# QRE1113_analogico_v11.net
KiCad netlist of a schematic drawn in EAGLE
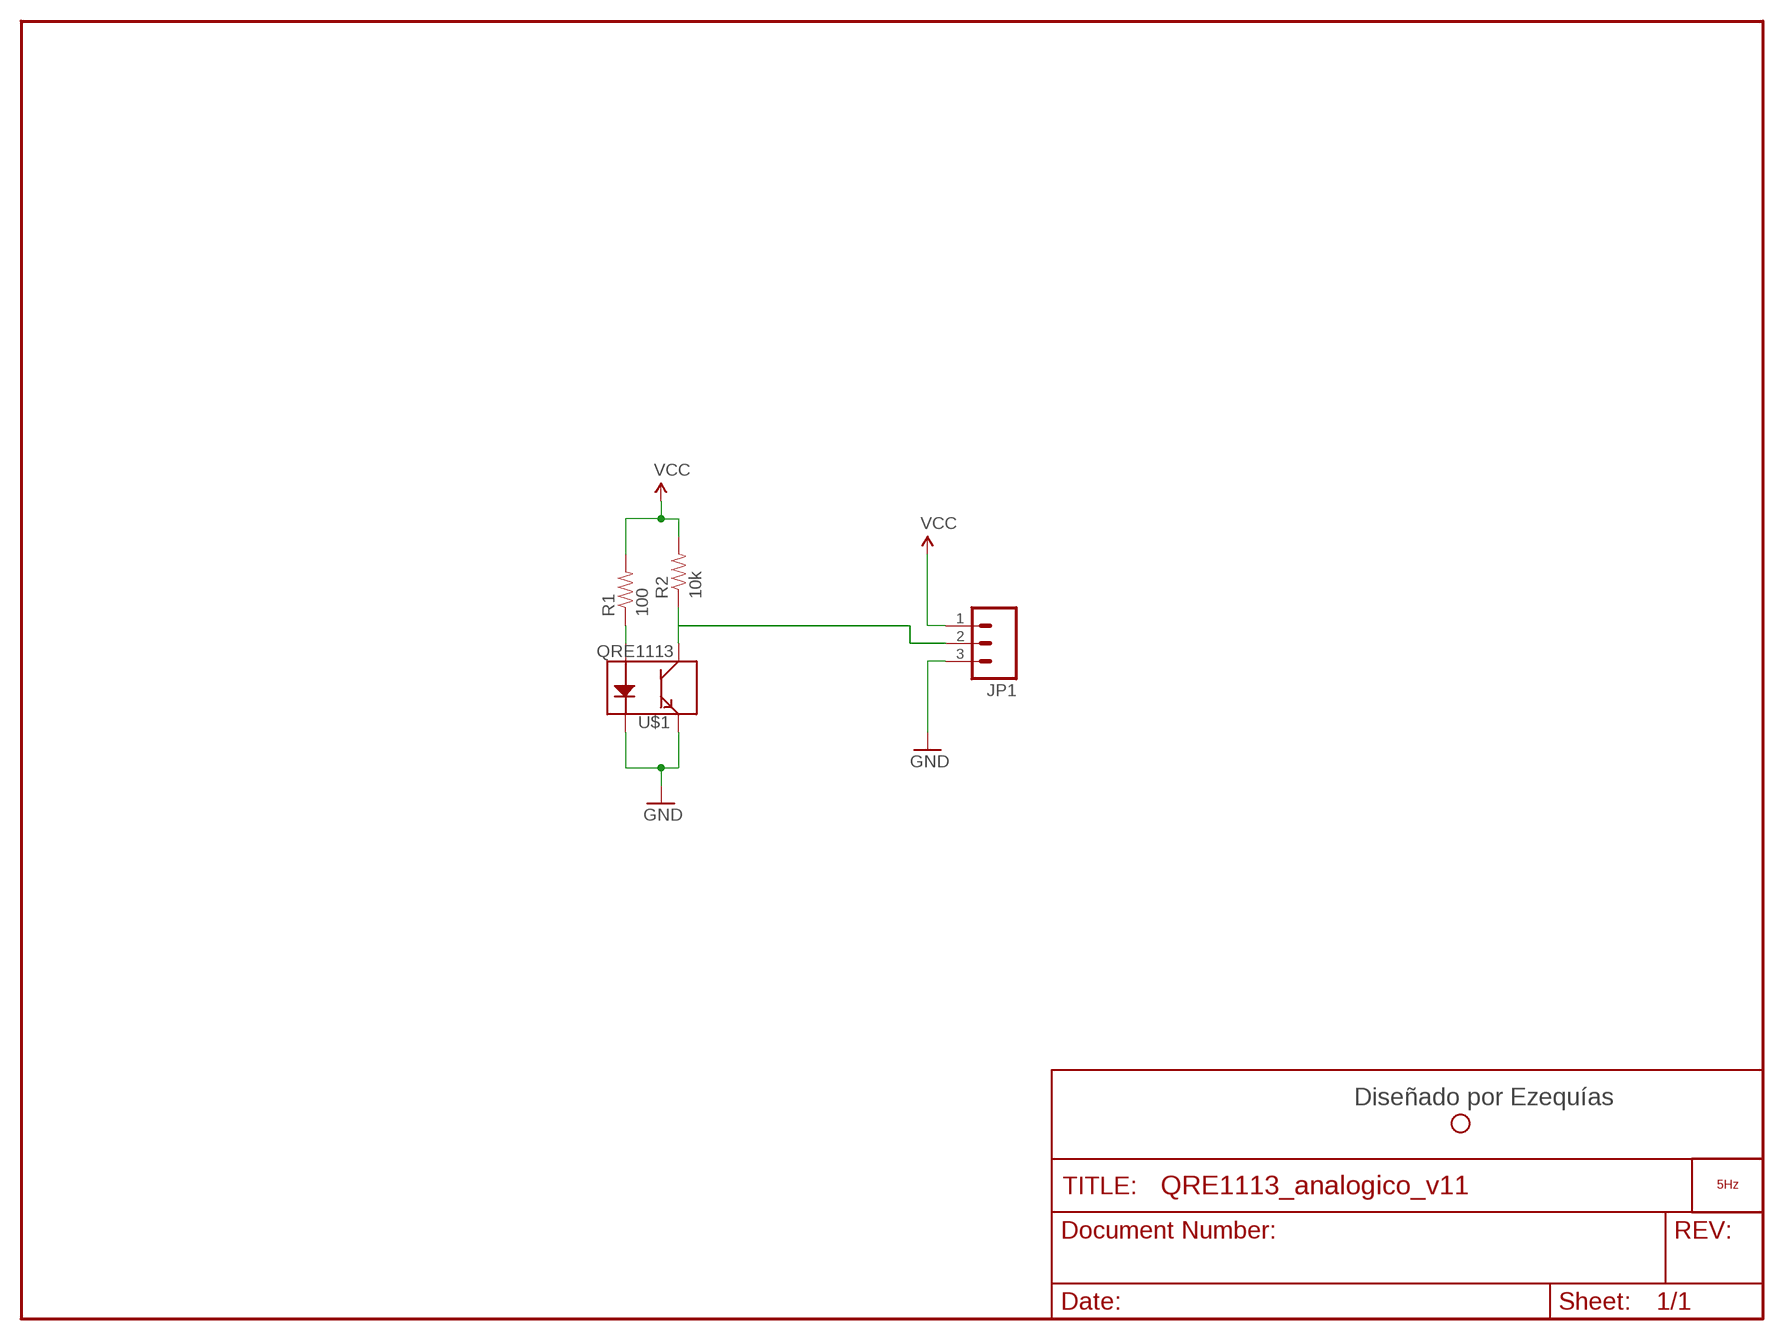
[diagram p0: schematic, sheet 1]

(export (version "E")
  (design (tool "Eeschema 10.0.6"))
  (components
    (comp (ref "JP1")
      (value "M03PTH")
      (footprint "eagle-import:1X03")
      (libsource (lib "eagle-import") (part "M03PTH"))
    )
    (comp (ref "JP2")
      (value "STAND-OFF")
      (footprint "eagle-import:STAND-OFF")
      (libsource (lib "eagle-import") (part "STAND-OFF"))
    )
    (comp (ref "LOGO1")
      (value "LOGO_5HZ_CIRC_5MM")
      (footprint "eagle-import:5HZ_LOGO_CIRC_5MM")
      (libsource (lib "eagle-import") (part "LOGO_5HZ_CIRC_5MM"))
    )
    (comp (ref "R1")
      (value "100")
      (footprint "eagle-import:0603-RES")
      (libsource (lib "eagle-import") (part "RESISTOR0603-RES"))
    )
    (comp (ref "R2")
      (value "10k")
      (footprint "eagle-import:0603-RES")
      (libsource (lib "eagle-import") (part "RESISTOR0603-RES"))
    )
    (comp (ref "U$1")
      (value "QRE1113")
      (footprint "eagle-import:QRE1113")
      (libsource (lib "eagle-import") (part "QRE1113"))
    )
  )
  (nets
    (net (code "1") (name "GND") (class "Default")
      (node (ref "JP1") (pin "3") (pinfunction "3_3") (pintype "passive"))
      (node (ref "U$1") (pin "2") (pinfunction "K_2") (pintype "bidirectional"))
      (node (ref "U$1") (pin "4") (pinfunction "E_4") (pintype "bidirectional"))
    )
    (net (code "2") (name "Net-(U$1-A)") (class "Default")
      (node (ref "R1") (pin "1") (pinfunction "1_1") (pintype "passive"))
      (node (ref "U$1") (pin "1") (pinfunction "A_1") (pintype "bidirectional"))
    )
    (net (code "3") (name "Net-(U$1-C)") (class "Default")
      (node (ref "JP1") (pin "2") (pinfunction "2_2") (pintype "passive"))
      (node (ref "R2") (pin "1") (pinfunction "1_1") (pintype "passive"))
      (node (ref "U$1") (pin "3") (pinfunction "C_3") (pintype "bidirectional"))
    )
    (net (code "4") (name "VCC") (class "Default")
      (node (ref "JP1") (pin "1") (pinfunction "1_1") (pintype "passive"))
      (node (ref "R1") (pin "2") (pinfunction "2_2") (pintype "passive"))
      (node (ref "R2") (pin "2") (pinfunction "2_2") (pintype "passive"))
    )
  )
)
